# MagusConnectors.net
KiCad netlist of a schematic drawn in EAGLE
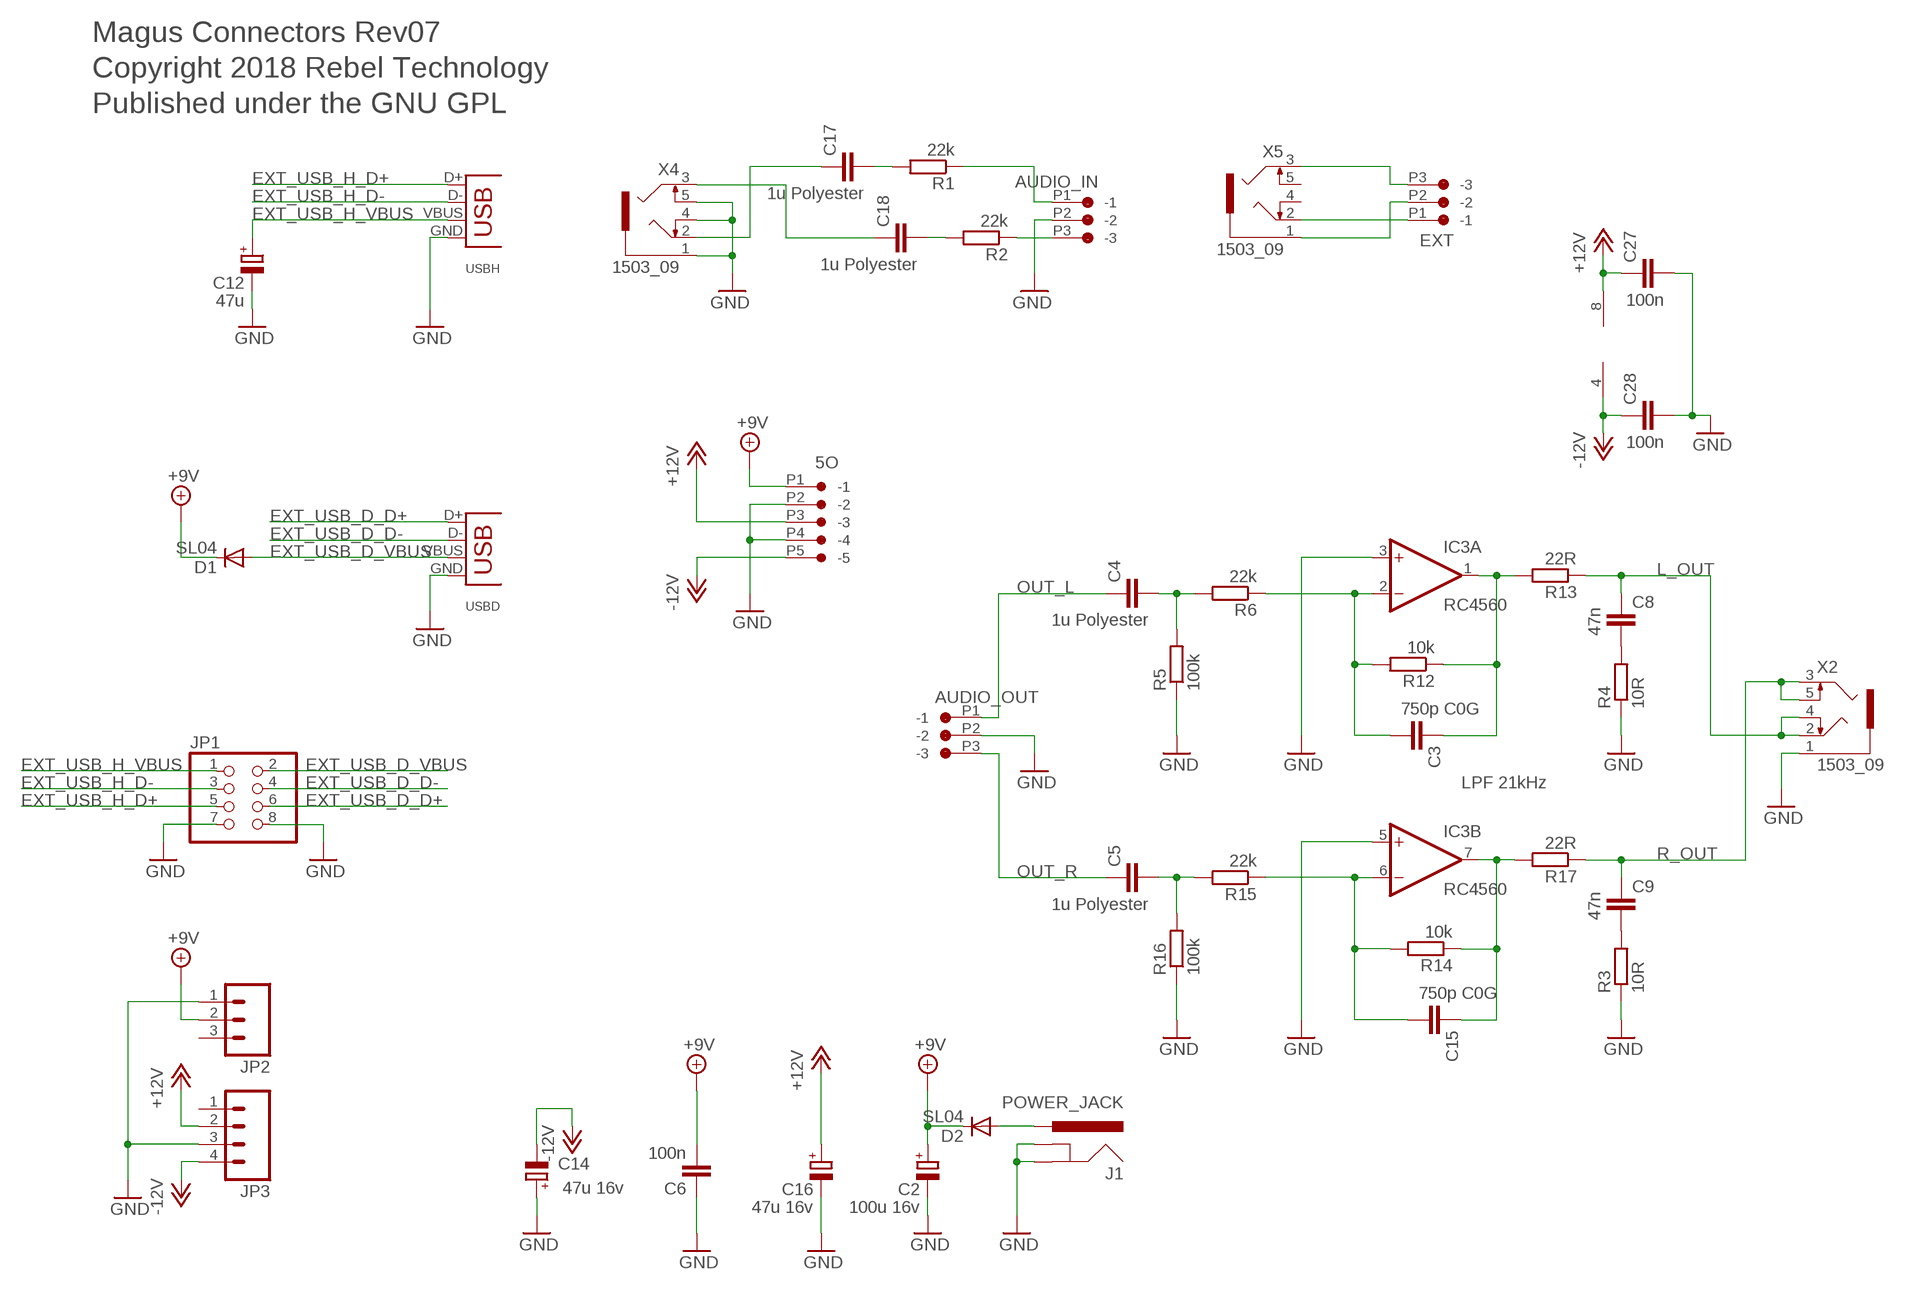
[diagram p0: schematic, sheet 1]

(export (version "E")
  (design (tool "Eeschema 10.0.6"))
  (components
    (comp (ref "5O")
      (value "CON-JST_PH_5W")
      (footprint "eagle-import:CON-JST_PH_5W")
      (libsource (lib "eagle-import") (part "CON-JST_PH_5W"))
    )
    (comp (ref "AUDIO_IN")
      (value "CON-JST_PH_3W")
      (footprint "eagle-import:CON-JST_PH_3W")
      (libsource (lib "eagle-import") (part "CON-JST_PH_3W"))
    )
    (comp (ref "AUDIO_OUT")
      (value "CON-JST_PH_3W")
      (footprint "eagle-import:CON-JST_PH_3W")
      (libsource (lib "eagle-import") (part "CON-JST_PH_3W"))
    )
    (comp (ref "C2")
      (value "100u 16v")
      (footprint "eagle-import:PANASONIC_D")
      (libsource (lib "eagle-import") (part "CPOL-EUD"))
    )
    (comp (ref "C3")
      (value "750p C0G")
      (footprint "eagle-import:C0603")
      (libsource (lib "eagle-import") (part "C-EUC0603"))
    )
    (comp (ref "C4")
      (value "1u Polyester")
      (footprint "eagle-import:C1210")
      (libsource (lib "eagle-import") (part "C-EUC1210"))
    )
    (comp (ref "C5")
      (value "1u Polyester")
      (footprint "eagle-import:C1210")
      (libsource (lib "eagle-import") (part "C-EUC1210"))
    )
    (comp (ref "C6")
      (value "100n")
      (footprint "eagle-import:C0603")
      (libsource (lib "eagle-import") (part "rcl_C-EUC0603"))
    )
    (comp (ref "C8")
      (value "47n")
      (footprint "eagle-import:C0603")
      (libsource (lib "eagle-import") (part "C-EUC0603"))
    )
    (comp (ref "C9")
      (value "47n")
      (footprint "eagle-import:C0603")
      (libsource (lib "eagle-import") (part "C-EUC0603"))
    )
    (comp (ref "C12")
      (value "47u")
      (footprint "eagle-import:PANASONIC_B")
      (libsource (lib "eagle-import") (part "CPOL-EUB"))
    )
    (comp (ref "C14")
      (value "47u 16v")
      (footprint "eagle-import:PANASONIC_B")
      (libsource (lib "eagle-import") (part "CPOL-EUB"))
    )
    (comp (ref "C15")
      (value "750p C0G")
      (footprint "eagle-import:C0603")
      (libsource (lib "eagle-import") (part "C-EUC0603"))
    )
    (comp (ref "C16")
      (value "47u 16v")
      (footprint "eagle-import:PANASONIC_B")
      (libsource (lib "eagle-import") (part "CPOL-EUB"))
    )
    (comp (ref "C17")
      (value "1u Polyester")
      (footprint "eagle-import:C1210")
      (libsource (lib "eagle-import") (part "C-EUC1210"))
    )
    (comp (ref "C18")
      (value "1u Polyester")
      (footprint "eagle-import:C1210")
      (libsource (lib "eagle-import") (part "C-EUC1210"))
    )
    (comp (ref "C27")
      (value "100n")
      (footprint "eagle-import:C0603")
      (libsource (lib "eagle-import") (part "C-EUC0603"))
    )
    (comp (ref "C28")
      (value "100n")
      (footprint "eagle-import:C0603")
      (libsource (lib "eagle-import") (part "C-EUC0603"))
    )
    (comp (ref "D1")
      (value "SL04")
      (footprint "eagle-import:SMA-DIODE")
      (libsource (lib "eagle-import") (part "DIODESMA"))
    )
    (comp (ref "D2")
      (value "SL04")
      (footprint "eagle-import:SMA-DIODE")
      (libsource (lib "eagle-import") (part "DIODESMA"))
    )
    (comp (ref "EXT")
      (value "CON-JST_PH_3W")
      (footprint "eagle-import:CON-JST_PH_3W")
      (libsource (lib "eagle-import") (part "CON-JST_PH_3W"))
    )
    (comp (ref "IC3")
      (value "RC4560")
      (footprint "eagle-import:SO08")
      (libsource (lib "eagle-import") (part "NE5532D"))
    )
    (comp (ref "J1")
      (value "POWER_JACK")
      (footprint "eagle-import:DC_JACK_SLOT")
      (libsource (lib "eagle-import") (part "POWER_JACK"))
    )
    (comp (ref "JP1")
      (value "PINHD-2X4")
      (footprint "eagle-import:2X04")
      (libsource (lib "eagle-import") (part "PINHD-2X4"))
    )
    (comp (ref "JP2")
      (value "M03PTH")
      (footprint "eagle-import:1X03")
      (libsource (lib "eagle-import") (part "M03PTH"))
    )
    (comp (ref "JP3")
      (value "M04PTH")
      (footprint "eagle-import:1X04")
      (libsource (lib "eagle-import") (part "M04PTH"))
    )
    (comp (ref "R1")
      (value "22k")
      (footprint "eagle-import:R0603")
      (libsource (lib "eagle-import") (part "R-EU_R0603"))
    )
    (comp (ref "R2")
      (value "22k")
      (footprint "eagle-import:R0603")
      (libsource (lib "eagle-import") (part "R-EU_R0603"))
    )
    (comp (ref "R3")
      (value "10R")
      (footprint "eagle-import:R0603")
      (libsource (lib "eagle-import") (part "R-EU_R0603"))
    )
    (comp (ref "R4")
      (value "10R")
      (footprint "eagle-import:R0603")
      (libsource (lib "eagle-import") (part "R-EU_R0603"))
    )
    (comp (ref "R5")
      (value "100k")
      (footprint "eagle-import:R0603")
      (libsource (lib "eagle-import") (part "R-EU_R0603"))
    )
    (comp (ref "R6")
      (value "22k")
      (footprint "eagle-import:R0603")
      (libsource (lib "eagle-import") (part "R-EU_R0603"))
    )
    (comp (ref "R12")
      (value "10k")
      (footprint "eagle-import:R0603")
      (libsource (lib "eagle-import") (part "R-EU_R0603"))
    )
    (comp (ref "R13")
      (value "22R")
      (footprint "eagle-import:R0603")
      (libsource (lib "eagle-import") (part "R-EU_R0603"))
    )
    (comp (ref "R14")
      (value "10k")
      (footprint "eagle-import:R0603")
      (libsource (lib "eagle-import") (part "R-EU_R0603"))
    )
    (comp (ref "R15")
      (value "22k")
      (footprint "eagle-import:R0603")
      (libsource (lib "eagle-import") (part "R-EU_R0603"))
    )
    (comp (ref "R16")
      (value "100k")
      (footprint "eagle-import:R0603")
      (libsource (lib "eagle-import") (part "R-EU_R0603"))
    )
    (comp (ref "R17")
      (value "22R")
      (footprint "eagle-import:R0603")
      (libsource (lib "eagle-import") (part "R-EU_R0603"))
    )
    (comp (ref "USBD")
      (value "USB-B-H")
      (footprint "eagle-import:USB-B-H")
      (libsource (lib "eagle-import") (part "USB-B-H"))
    )
    (comp (ref "USBH")
      (value "USB-A-H")
      (footprint "eagle-import:USB-A-H")
      (libsource (lib "eagle-import") (part "USB-A-H"))
    )
    (comp (ref "X2")
      (value "1503_09")
      (footprint "eagle-import:1503_09")
      (libsource (lib "eagle-import") (part "1503_09"))
    )
    (comp (ref "X4")
      (value "1503_09")
      (footprint "eagle-import:1503_09")
      (libsource (lib "eagle-import") (part "1503_09"))
    )
    (comp (ref "X5")
      (value "1503_09")
      (footprint "eagle-import:1503_09")
      (libsource (lib "eagle-import") (part "1503_09"))
    )
  )
  (nets
    (net (code "1") (name "+9V") (class "Default")
      (node (ref "5O") (pin "P1") (pinfunction "-1_P1") (pintype "bidirectional"))
      (node (ref "C2") (pin "+") (pinfunction "+_+") (pintype "passive"))
      (node (ref "C6") (pin "2") (pinfunction "2_2") (pintype "passive"))
      (node (ref "D1") (pin "C") (pinfunction "C_C") (pintype "passive"))
      (node (ref "D2") (pin "C") (pinfunction "C_C") (pintype "passive"))
      (node (ref "JP2") (pin "2") (pinfunction "2_2") (pintype "passive"))
    )
    (net (code "2") (name "+12V") (class "Default")
      (node (ref "5O") (pin "P3") (pinfunction "-3_P3") (pintype "bidirectional"))
      (node (ref "C16") (pin "+") (pinfunction "+_+") (pintype "passive"))
      (node (ref "C27") (pin "1") (pinfunction "1_1") (pintype "passive"))
      (node (ref "IC3") (pin "8") (pinfunction "V+_8") (pintype "power_in"))
      (node (ref "JP3") (pin "2") (pinfunction "2_2") (pintype "passive"))
    )
    (net (code "3") (name "-12V") (class "Default")
      (node (ref "5O") (pin "P5") (pinfunction "-5_P5") (pintype "bidirectional"))
      (node (ref "C14") (pin "-") (pinfunction "-_-") (pintype "passive"))
      (node (ref "C28") (pin "1") (pinfunction "1_1") (pintype "passive"))
      (node (ref "IC3") (pin "4") (pinfunction "V-_4") (pintype "power_in"))
      (node (ref "JP3") (pin "4") (pinfunction "4_4") (pintype "passive"))
    )
    (net (code "4") (name "/EXT_USB_D_D+") (class "Default")
      (node (ref "JP1") (pin "6") (pinfunction "6_6") (pintype "passive"))
      (node (ref "USBD") (pin "D+") (pinfunction "D+_D+") (pintype "bidirectional"))
    )
    (net (code "5") (name "/EXT_USB_D_D-") (class "Default")
      (node (ref "JP1") (pin "4") (pinfunction "4_4") (pintype "passive"))
      (node (ref "USBD") (pin "D-") (pinfunction "D-_D-") (pintype "bidirectional"))
    )
    (net (code "6") (name "/EXT_USB_D_VBUS") (class "Default")
      (node (ref "D1") (pin "A") (pinfunction "A_A") (pintype "passive"))
      (node (ref "JP1") (pin "2") (pinfunction "2_2") (pintype "passive"))
      (node (ref "USBD") (pin "VBUS") (pinfunction "VBUS_VBUS") (pintype "bidirectional"))
    )
    (net (code "7") (name "/EXT_USB_H_D+") (class "Default")
      (node (ref "JP1") (pin "5") (pinfunction "5_5") (pintype "passive"))
      (node (ref "USBH") (pin "D+") (pinfunction "D+_D+") (pintype "bidirectional"))
    )
    (net (code "8") (name "/EXT_USB_H_D-") (class "Default")
      (node (ref "JP1") (pin "3") (pinfunction "3_3") (pintype "passive"))
      (node (ref "USBH") (pin "D-") (pinfunction "D-_D-") (pintype "bidirectional"))
    )
    (net (code "9") (name "/EXT_USB_H_VBUS") (class "Default")
      (node (ref "C12") (pin "+") (pinfunction "+_+") (pintype "passive"))
      (node (ref "JP1") (pin "1") (pinfunction "1_1") (pintype "passive"))
      (node (ref "USBH") (pin "VBUS") (pinfunction "VBUS_VBUS") (pintype "bidirectional"))
    )
    (net (code "10") (name "/L_OUT") (class "Default")
      (node (ref "C8") (pin "1") (pinfunction "1_1") (pintype "passive"))
      (node (ref "R13") (pin "1") (pinfunction "1_1") (pintype "passive"))
      (node (ref "X2") (pin "2") (pinfunction "2_2") (pintype "passive"))
      (node (ref "X2") (pin "4") (pinfunction "4_4") (pintype "passive"))
    )
    (net (code "11") (name "/OUT_L") (class "Default")
      (node (ref "AUDIO_OUT") (pin "P1") (pinfunction "-1_P1") (pintype "bidirectional"))
      (node (ref "C4") (pin "1") (pinfunction "1_1") (pintype "passive"))
    )
    (net (code "12") (name "/OUT_R") (class "Default")
      (node (ref "AUDIO_OUT") (pin "P3") (pinfunction "-3_P3") (pintype "bidirectional"))
      (node (ref "C5") (pin "1") (pinfunction "1_1") (pintype "passive"))
    )
    (net (code "13") (name "/R_OUT") (class "Default")
      (node (ref "C9") (pin "1") (pinfunction "1_1") (pintype "passive"))
      (node (ref "R17") (pin "1") (pinfunction "1_1") (pintype "passive"))
      (node (ref "X2") (pin "3") (pinfunction "3_3") (pintype "passive"))
      (node (ref "X2") (pin "5") (pinfunction "5_5") (pintype "passive"))
    )
    (net (code "14") (name "GND") (class "Default")
      (node (ref "5O") (pin "P2") (pinfunction "-2_P2") (pintype "bidirectional"))
      (node (ref "5O") (pin "P4") (pinfunction "-4_P4") (pintype "bidirectional"))
      (node (ref "AUDIO_IN") (pin "P2") (pinfunction "-2_P2") (pintype "bidirectional"))
      (node (ref "AUDIO_OUT") (pin "P2") (pinfunction "-2_P2") (pintype "bidirectional"))
      (node (ref "C12") (pin "-") (pinfunction "-_-") (pintype "passive"))
      (node (ref "C14") (pin "+") (pinfunction "+_+") (pintype "passive"))
      (node (ref "C16") (pin "-") (pinfunction "-_-") (pintype "passive"))
      (node (ref "C2") (pin "-") (pinfunction "-_-") (pintype "passive"))
      (node (ref "C27") (pin "2") (pinfunction "2_2") (pintype "passive"))
      (node (ref "C28") (pin "2") (pinfunction "2_2") (pintype "passive"))
      (node (ref "C6") (pin "1") (pinfunction "1_1") (pintype "passive"))
      (node (ref "IC3") (pin "3") (pinfunction "+IN_3") (pintype "input"))
      (node (ref "IC3") (pin "5") (pinfunction "+IN_5") (pintype "input"))
      (node (ref "J1") (pin "GND") (pinfunction "GND_GND") (pintype "bidirectional"))
      (node (ref "J1") (pin "GNDBREAK") (pinfunction "GNDBREAK_GNDBREAK") (pintype "bidirectional"))
      (node (ref "JP1") (pin "7") (pinfunction "7_7") (pintype "passive"))
      (node (ref "JP1") (pin "8") (pinfunction "8_8") (pintype "passive"))
      (node (ref "JP2") (pin "1") (pinfunction "1_1") (pintype "passive"))
      (node (ref "JP3") (pin "3") (pinfunction "3_3") (pintype "passive"))
      (node (ref "R16") (pin "1") (pinfunction "1_1") (pintype "passive"))
      (node (ref "R3") (pin "1") (pinfunction "1_1") (pintype "passive"))
      (node (ref "R4") (pin "1") (pinfunction "1_1") (pintype "passive"))
      (node (ref "R5") (pin "1") (pinfunction "1_1") (pintype "passive"))
      (node (ref "USBD") (pin "GND") (pinfunction "GND_GND") (pintype "bidirectional"))
      (node (ref "USBH") (pin "GND") (pinfunction "GND_GND") (pintype "bidirectional"))
      (node (ref "X2") (pin "1") (pinfunction "1_1") (pintype "passive"))
      (node (ref "X4") (pin "1") (pinfunction "1_1") (pintype "passive"))
      (node (ref "X4") (pin "4") (pinfunction "4_4") (pintype "passive"))
      (node (ref "X4") (pin "5") (pinfunction "5_5") (pintype "passive"))
    )
    (net (code "15") (name "Net-(AUDIO_IN--1)") (class "Default")
      (node (ref "AUDIO_IN") (pin "P1") (pinfunction "-1_P1") (pintype "bidirectional"))
      (node (ref "R1") (pin "1") (pinfunction "1_1") (pintype "passive"))
    )
    (net (code "16") (name "Net-(AUDIO_IN--3)") (class "Default")
      (node (ref "AUDIO_IN") (pin "P3") (pinfunction "-3_P3") (pintype "bidirectional"))
      (node (ref "R2") (pin "1") (pinfunction "1_1") (pintype "passive"))
    )
    (net (code "17") (name "Net-(C4-Pad2)") (class "Default")
      (node (ref "C4") (pin "2") (pinfunction "2_2") (pintype "passive"))
      (node (ref "R5") (pin "2") (pinfunction "2_2") (pintype "passive"))
      (node (ref "R6") (pin "2") (pinfunction "2_2") (pintype "passive"))
    )
    (net (code "18") (name "Net-(C5-Pad2)") (class "Default")
      (node (ref "C5") (pin "2") (pinfunction "2_2") (pintype "passive"))
      (node (ref "R15") (pin "2") (pinfunction "2_2") (pintype "passive"))
      (node (ref "R16") (pin "2") (pinfunction "2_2") (pintype "passive"))
    )
    (net (code "19") (name "Net-(C8-Pad2)") (class "Default")
      (node (ref "C8") (pin "2") (pinfunction "2_2") (pintype "passive"))
      (node (ref "R4") (pin "2") (pinfunction "2_2") (pintype "passive"))
    )
    (net (code "20") (name "Net-(C9-Pad2)") (class "Default")
      (node (ref "C9") (pin "2") (pinfunction "2_2") (pintype "passive"))
      (node (ref "R3") (pin "2") (pinfunction "2_2") (pintype "passive"))
    )
    (net (code "21") (name "Net-(C17-Pad1)") (class "Default")
      (node (ref "C17") (pin "1") (pinfunction "1_1") (pintype "passive"))
      (node (ref "X4") (pin "2") (pinfunction "2_2") (pintype "passive"))
    )
    (net (code "22") (name "Net-(C17-Pad2)") (class "Default")
      (node (ref "C17") (pin "2") (pinfunction "2_2") (pintype "passive"))
      (node (ref "R1") (pin "2") (pinfunction "2_2") (pintype "passive"))
    )
    (net (code "23") (name "Net-(C18-Pad1)") (class "Default")
      (node (ref "C18") (pin "1") (pinfunction "1_1") (pintype "passive"))
      (node (ref "X4") (pin "3") (pinfunction "3_3") (pintype "passive"))
    )
    (net (code "24") (name "Net-(C18-Pad2)") (class "Default")
      (node (ref "C18") (pin "2") (pinfunction "2_2") (pintype "passive"))
      (node (ref "R2") (pin "2") (pinfunction "2_2") (pintype "passive"))
    )
    (net (code "25") (name "Net-(D2-PadA)") (class "Default")
      (node (ref "D2") (pin "A") (pinfunction "A_A") (pintype "passive"))
      (node (ref "J1") (pin "PWR") (pinfunction "PWR_PWR") (pintype "bidirectional"))
    )
    (net (code "26") (name "Net-(EXT--1)") (class "Default")
      (node (ref "EXT") (pin "P1") (pinfunction "-1_P1") (pintype "bidirectional"))
      (node (ref "X5") (pin "2") (pinfunction "2_2") (pintype "passive"))
    )
    (net (code "27") (name "Net-(EXT--2)") (class "Default")
      (node (ref "EXT") (pin "P2") (pinfunction "-2_P2") (pintype "bidirectional"))
      (node (ref "X5") (pin "1") (pinfunction "1_1") (pintype "passive"))
    )
    (net (code "28") (name "Net-(EXT--3)") (class "Default")
      (node (ref "EXT") (pin "P3") (pinfunction "-3_P3") (pintype "bidirectional"))
      (node (ref "X5") (pin "3") (pinfunction "3_3") (pintype "passive"))
    )
    (net (code "29") (name "Net-(IC3A--IN)") (class "Default")
      (node (ref "C3") (pin "2") (pinfunction "2_2") (pintype "passive"))
      (node (ref "IC3") (pin "2") (pinfunction "-IN_2") (pintype "input"))
      (node (ref "R12") (pin "2") (pinfunction "2_2") (pintype "passive"))
      (node (ref "R6") (pin "1") (pinfunction "1_1") (pintype "passive"))
    )
    (net (code "30") (name "Net-(IC3A-OUT)") (class "Default")
      (node (ref "C3") (pin "1") (pinfunction "1_1") (pintype "passive"))
      (node (ref "IC3") (pin "1") (pinfunction "OUT_1") (pintype "output"))
      (node (ref "R12") (pin "1") (pinfunction "1_1") (pintype "passive"))
      (node (ref "R13") (pin "2") (pinfunction "2_2") (pintype "passive"))
    )
    (net (code "31") (name "Net-(IC3B--IN)") (class "Default")
      (node (ref "C15") (pin "2") (pinfunction "2_2") (pintype "passive"))
      (node (ref "IC3") (pin "6") (pinfunction "-IN_6") (pintype "input"))
      (node (ref "R14") (pin "2") (pinfunction "2_2") (pintype "passive"))
      (node (ref "R15") (pin "1") (pinfunction "1_1") (pintype "passive"))
    )
    (net (code "32") (name "Net-(IC3B-OUT)") (class "Default")
      (node (ref "C15") (pin "1") (pinfunction "1_1") (pintype "passive"))
      (node (ref "IC3") (pin "7") (pinfunction "OUT_7") (pintype "output"))
      (node (ref "R14") (pin "1") (pinfunction "1_1") (pintype "passive"))
      (node (ref "R17") (pin "2") (pinfunction "2_2") (pintype "passive"))
    )
    (net (code "33") (name "unconnected-(JP2-Pad3)") (class "Default")
      (node (ref "JP2") (pin "3") (pinfunction "3_3") (pintype "passive"))
    )
    (net (code "34") (name "unconnected-(JP3-Pad1)") (class "Default")
      (node (ref "JP3") (pin "1") (pinfunction "1_1") (pintype "passive"))
    )
    (net (code "35") (name "unconnected-(X5-Pad4)") (class "Default")
      (node (ref "X5") (pin "4") (pinfunction "4_4") (pintype "passive"))
    )
    (net (code "36") (name "unconnected-(X5-Pad5)") (class "Default")
      (node (ref "X5") (pin "5") (pinfunction "5_5") (pintype "passive"))
    )
  )
)
